# cm5.net
KiCad netlist of a schematic drawn in Altium Designer
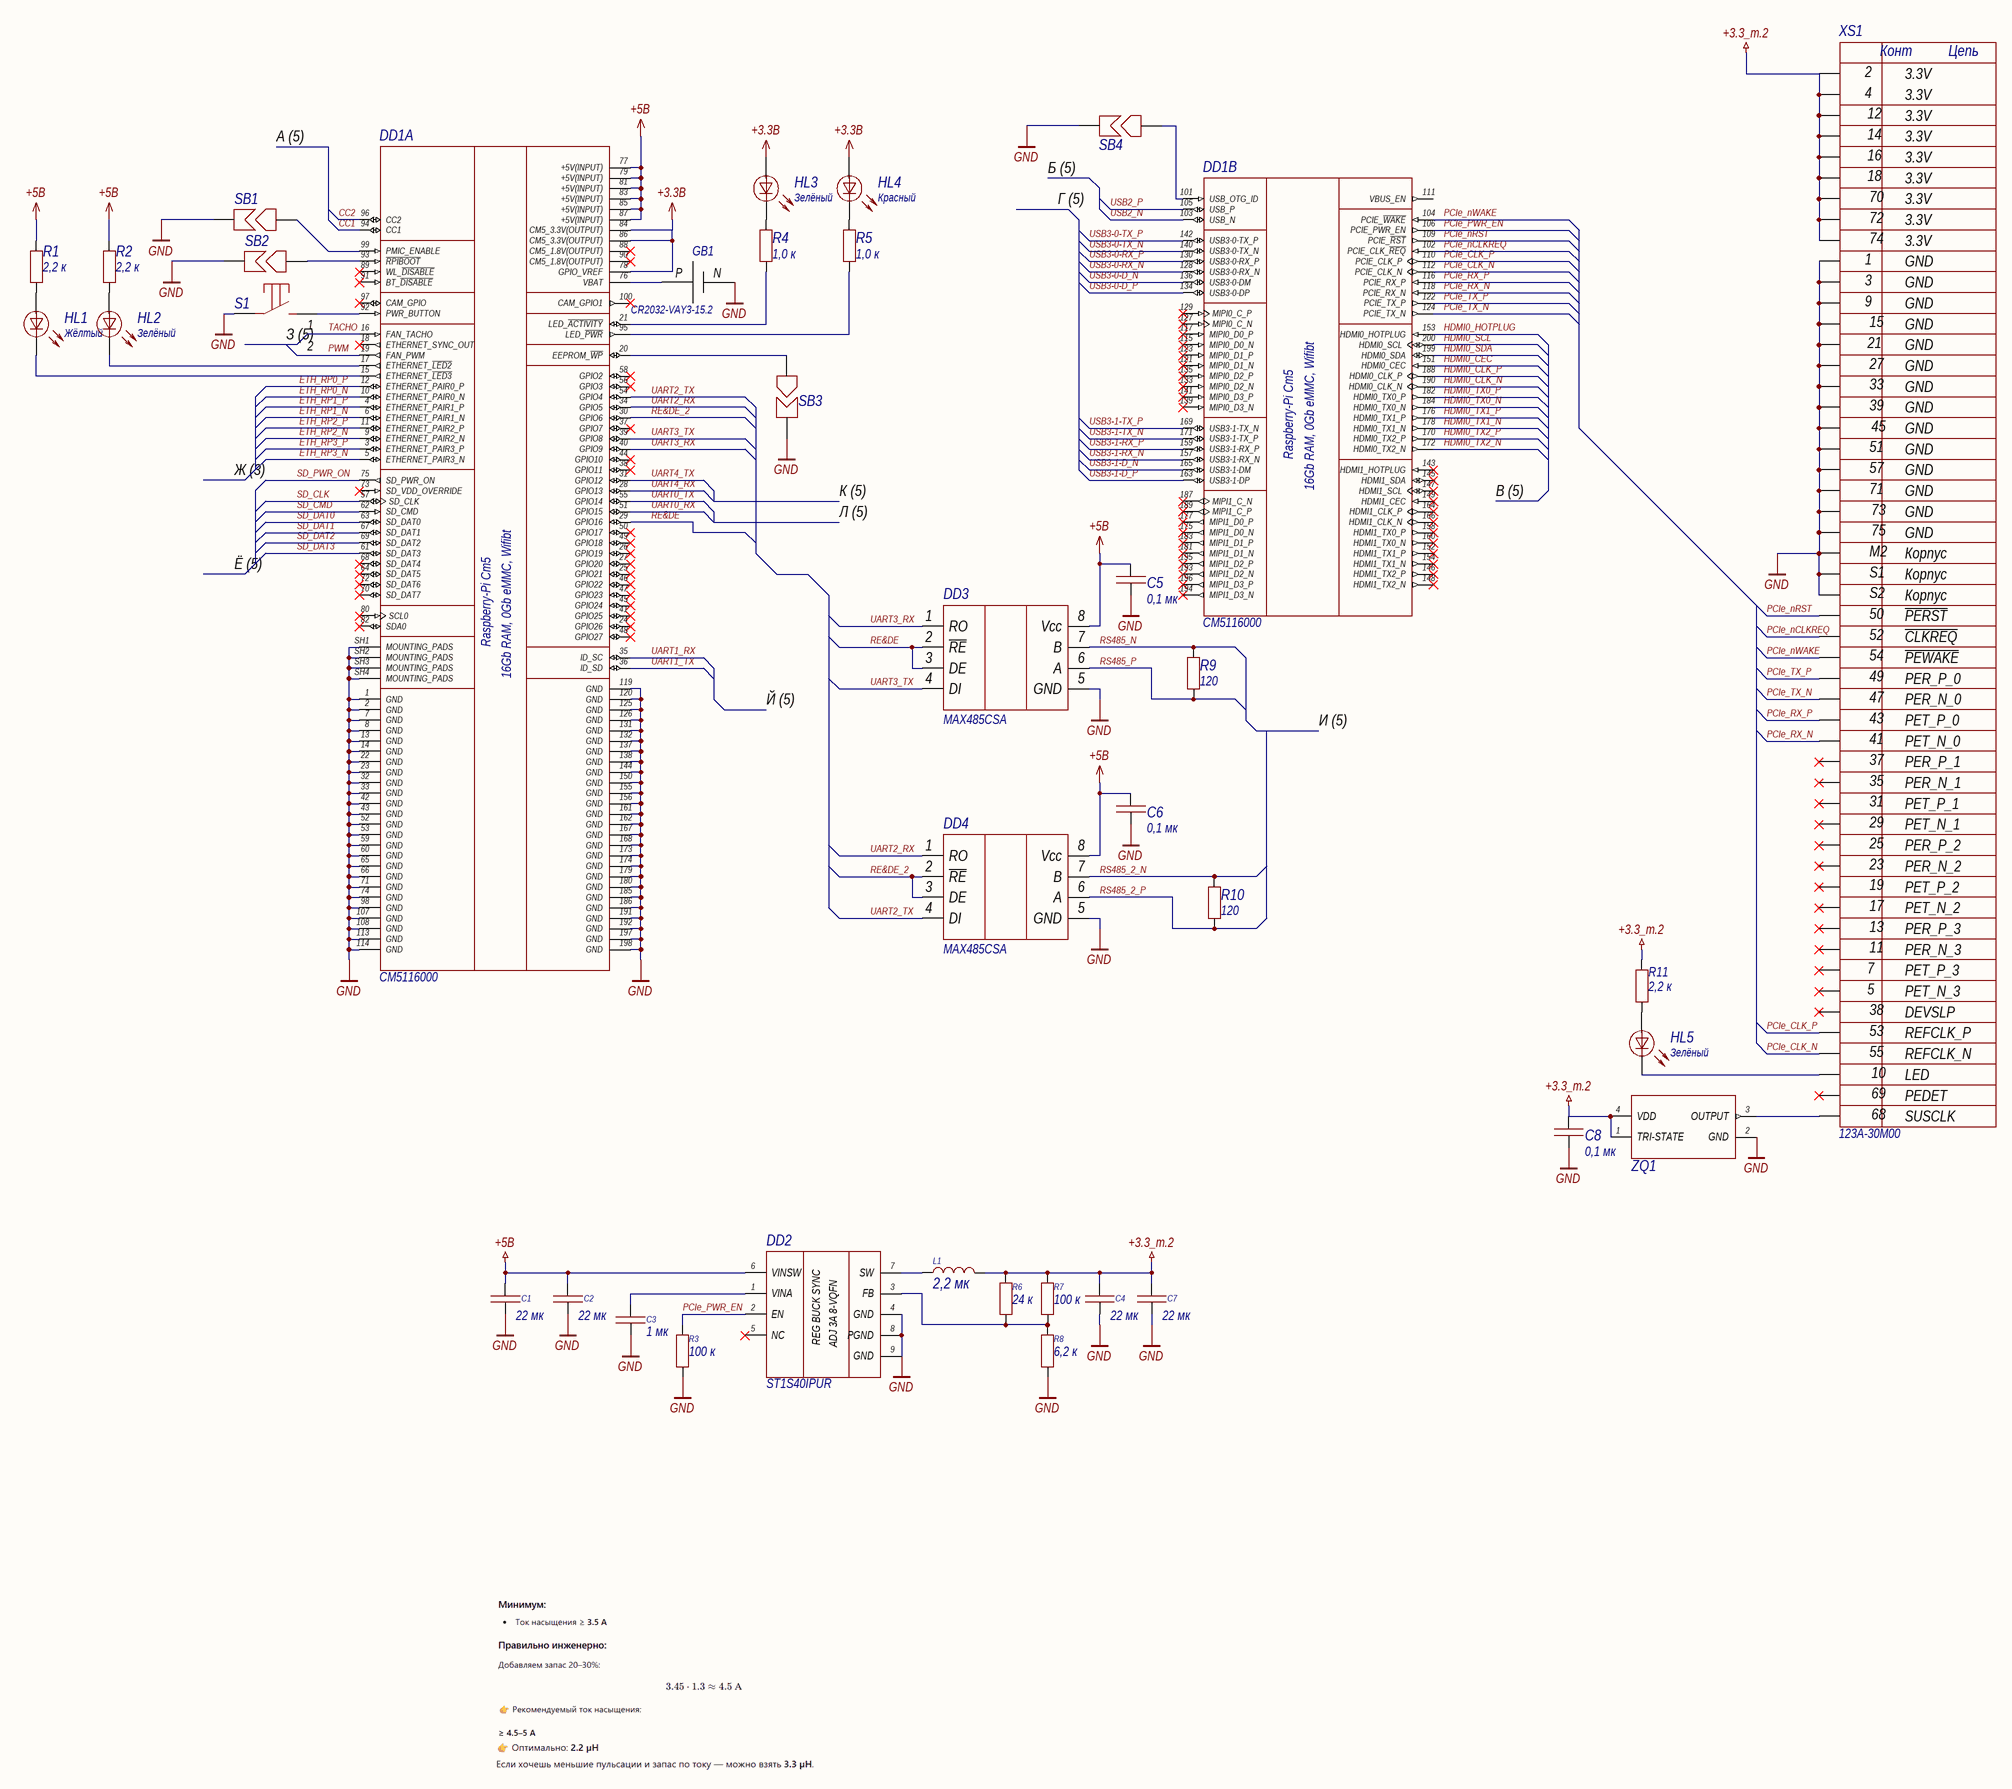
[diagram p0: cm5.SchDoc]

(export (version "E")
  (design (tool "Eeschema 10.0.6"))
  (components
    (comp (ref "C1")
      (value "22 мк")
      (footprint "1210C")
      (description "Конденсатор 1210C ёмкостью 22 мк 10%, 25 В, X7R")
      (fields (field (name "PART NUMBER") "Capacitor_22u_10_25V_X7R_1210C") (field (name "TOLERANCE") "10%"))
      (libsource (lib "Hydrolib") (part "Capacitor"))
    )
    (comp (ref "C2")
      (value "22 мк")
      (footprint "1210C")
      (description "Конденсатор 1210C ёмкостью 22 мк 10%, 25 В, X7R")
      (fields (field (name "PART NUMBER") "Capacitor_22u_10_25V_X7R_1210C") (field (name "TOLERANCE") "10%"))
      (libsource (lib "Hydrolib") (part "Capacitor"))
    )
    (comp (ref "C3")
      (value "1 мк")
      (footprint "0603C")
      (description "Конденсатор 0603C ёмкостью 1 мк 10%, 50 В, X7R")
      (fields (field (name "PART NUMBER") "Capacitor_1u_10_50V_X7R_0603C") (field (name "TOLERANCE") "10%"))
      (libsource (lib "Hydrolib") (part "Capacitor"))
    )
    (comp (ref "C4")
      (value "22 мк")
      (footprint "1210C")
      (description "Конденсатор 1210C ёмкостью 22 мк 10%, 25 В, X7R")
      (fields (field (name "PART NUMBER") "Capacitor_22u_10_25V_X7R_1210C") (field (name "TOLERANCE") "10%"))
      (libsource (lib "Hydrolib") (part "Capacitor"))
    )
    (comp (ref "C5")
      (value "0,1 мк")
      (footprint "0603C")
      (description "Конденсатор 0603C ёмкостью 0,1 мк 10%, 50 В, X7R")
      (fields (field (name "PART NUMBER") "Capacitor_0,1u_10_50V_X7R_0603C") (field (name "TOLERANCE") "10%"))
      (libsource (lib "Hydrolib") (part "Capacitor"))
    )
    (comp (ref "C6")
      (value "0,1 мк")
      (footprint "0603C")
      (description "Конденсатор 0603C ёмкостью 0,1 мк 10%, 50 В, X7R")
      (fields (field (name "PART NUMBER") "Capacitor_0,1u_10_50V_X7R_0603C") (field (name "TOLERANCE") "10%"))
      (libsource (lib "Hydrolib") (part "Capacitor"))
    )
    (comp (ref "C7")
      (value "22 мк")
      (footprint "1210C")
      (description "Конденсатор 1210C ёмкостью 22 мк 10%, 25 В, X7R")
      (fields (field (name "PART NUMBER") "Capacitor_22u_10_25V_X7R_1210C") (field (name "TOLERANCE") "10%"))
      (libsource (lib "Hydrolib") (part "Capacitor"))
    )
    (comp (ref "C8")
      (value "0,1 мк")
      (footprint "0603C")
      (description "Конденсатор 0603C ёмкостью 0,1 мк 10%, 50 В, X7R")
      (fields (field (name "PART NUMBER") "Capacitor_0,1u_10_50V_X7R_0603C") (field (name "TOLERANCE") "10%"))
      (libsource (lib "Hydrolib") (part "Capacitor"))
    )
    (comp (ref "DD1")
      (value "CM5116000")
      (footprint "CM5116000")
      (description "Raspberry-Pi Cm5 16Gb RAM, 0Gb eMMC, Wifibt")
      (fields
        (field (name "MF") "Raspberry Pi")
        (field (name "MP") "CM5108064B")
        (field (name "АВТОР") "rreali")
      )
      (libsource (lib "Hydrolib") (part "CM5116000"))
    )
    (comp (ref "DD2")
      (value "ST1S40IPUR")
      (footprint "VFQFPN8-4X4")
      (description "Преобразователь постоянного тока понижающий синхронный подстраиваемый 3А")
      (fields (field (name "MF") "STMicroelectronics") (field (name "АВТОР") "rreali"))
      (libsource (lib "Hydrolib") (part "ST1S40IPUR"))
    )
    (comp (ref "DD3")
      (value "MAX485CSA")
      (footprint "SOIC-8")
      (description "RS-485 приёмопередатчик")
      (libsource (lib "Hydrolib") (part "MAX485CSA"))
    )
    (comp (ref "DD4")
      (value "MAX485CSA")
      (footprint "SOIC-8")
      (description "RS-485 приёмопередатчик")
      (libsource (lib "Hydrolib") (part "MAX485CSA"))
    )
    (comp (ref "GB1")
      (value "CR2032-VAY3-15.2")
      (footprint "CR2032-VAY3-15.2")
      (description "Li, MnO2 батарея типоразмера R20, 3В, 0.22Ач, приваренные выводы, -20...60 °C")
      (fields (field (name "АВТОР") "rreali"))
      (libsource (lib "Hydrolib") (part "Battery"))
    )
    (comp (ref "HL1")
      (value "Жёлтый")
      (footprint "0603D_yellow")
      (description "Светодиод 0603 Жёлтый")
      (fields (field (name "PART NUMBER") "LED 0603 YELLOW") (field (name "АВТОР") "rreali"))
      (libsource (lib "Hydrolib") (part "LED"))
    )
    (comp (ref "HL2")
      (value "Зелёный")
      (footprint "0603D_green")
      (description "Светодиод 0603 Зелёный")
      (fields (field (name "PART NUMBER") "LED 0603 GREEN") (field (name "АВТОР") "rreali"))
      (libsource (lib "Hydrolib") (part "LED"))
    )
    (comp (ref "HL3")
      (value "Зелёный")
      (footprint "0603D_green")
      (description "Светодиод 0603 Зелёный")
      (fields (field (name "PART NUMBER") "LED 0603 GREEN") (field (name "АВТОР") "rreali"))
      (libsource (lib "Hydrolib") (part "LED"))
    )
    (comp (ref "HL4")
      (value "Красный")
      (footprint "0603D_red")
      (description "Светодиод 0603 Красный")
      (fields (field (name "PART NUMBER") "LED 0603 RED") (field (name "АВТОР") "rreali"))
      (libsource (lib "Hydrolib") (part "LED"))
    )
    (comp (ref "HL5")
      (value "Зелёный")
      (footprint "0603D_green")
      (description "Светодиод 0603 Зелёный")
      (fields (field (name "PART NUMBER") "LED 0603 GREEN") (field (name "АВТОР") "rreali"))
      (libsource (lib "Hydrolib") (part "LED"))
    )
    (comp (ref "L1")
      (value "2,2 мк")
      (footprint "IHLP-2020")
      (description "Катушка индуктивности SMD экранированная 2,2мкГн ±20% 4,2A 50,1мОм 2020 лента на катушке")
      (fields (field (name "PART NUMBER") "IHLP2020BZER2R2M01") (field (name "АВТОР") "rreali"))
      (libsource (lib "Hydrolib") (part "Inductance"))
    )
    (comp (ref "R1")
      (value "2,2 к")
      (footprint "0603R")
      (description "Резистор номиналом 2,2 кОм 1%")
      (fields (field (name "PART NUMBER") "Resistor_2.2k_1_0603") (field (name "TOLERANCE") "1%"))
      (libsource (lib "Hydrolib") (part "Resistor"))
    )
    (comp (ref "R2")
      (value "2,2 к")
      (footprint "0603R")
      (description "Резистор номиналом 2,2 кОм 1%")
      (fields (field (name "PART NUMBER") "Resistor_2.2k_1_0603") (field (name "TOLERANCE") "1%"))
      (libsource (lib "Hydrolib") (part "Resistor"))
    )
    (comp (ref "R3")
      (value "100 к")
      (footprint "0603R")
      (description "Резистор номиналом 100 кОм 1%")
      (fields (field (name "PART NUMBER") "Resistor_100k_1_0603") (field (name "TOLERANCE") "1%"))
      (libsource (lib "Hydrolib") (part "Resistor"))
    )
    (comp (ref "R4")
      (value "1,0 к")
      (footprint "0603R")
      (description "Резистор номиналом 1,0 кОм 1%")
      (fields (field (name "PART NUMBER") "Resistor_1.0k_1_0603") (field (name "TOLERANCE") "1%"))
      (libsource (lib "") (part "Resistor_1"))
    )
    (comp (ref "R5")
      (value "1,0 к")
      (footprint "0603R")
      (description "Резистор номиналом 1,0 кОм 1%")
      (fields (field (name "PART NUMBER") "Resistor_1.0k_1_0603") (field (name "TOLERANCE") "1%"))
      (libsource (lib "") (part "Resistor_1"))
    )
    (comp (ref "R6")
      (value "24 к")
      (footprint "0603R")
      (description "Резистор номиналом 24 кОм 1%")
      (fields (field (name "PART NUMBER") "Resistor_24k_1_0603") (field (name "TOLERANCE") "1%"))
      (libsource (lib "Hydrolib") (part "Resistor"))
    )
    (comp (ref "R7")
      (value "100 к")
      (footprint "0603R")
      (description "Резистор номиналом 100 кОм 1%")
      (fields (field (name "PART NUMBER") "Resistor_100k_1_0603") (field (name "TOLERANCE") "1%"))
      (libsource (lib "Hydrolib") (part "Resistor"))
    )
    (comp (ref "R8")
      (value "6,2 к")
      (footprint "0603R")
      (description "Резистор номиналом 6,2 кОм 1%")
      (fields (field (name "PART NUMBER") "Resistor_6.2k_1_0603") (field (name "TOLERANCE") "1%"))
      (libsource (lib "Hydrolib") (part "Resistor"))
    )
    (comp (ref "R9")
      (value "120")
      (footprint "1206R")
      (description "Резистор номиналом 120 Ом 1%")
      (fields (field (name "PART NUMBER") "Resistor_120_1_0603") (field (name "TOLERANCE") "1%"))
      (libsource (lib "Hydrolib") (part "Resistor"))
    )
    (comp (ref "R10")
      (value "120")
      (footprint "1206R")
      (description "Резистор номиналом 120 Ом 1%")
      (fields (field (name "PART NUMBER") "Resistor_120_1_0603") (field (name "TOLERANCE") "1%"))
      (libsource (lib "Hydrolib") (part "Resistor"))
    )
    (comp (ref "R11")
      (value "2,2 к")
      (footprint "0603R")
      (description "Резистор номиналом 2,2 кОм 1%")
      (fields (field (name "PART NUMBER") "Resistor_2.2k_1_0603") (field (name "TOLERANCE") "1%"))
      (libsource (lib "Hydrolib") (part "Resistor"))
    )
    (comp (ref "S1")
      (value "TSS-TD-19XA-XTR")
      (footprint "TSS-TD-19XA-XTR")
      (description "Тактовая кнопка")
      (fields (field (name "АВТОР") "glebmih"))
      (libsource (lib "Hydrolib") (part "Tact_button"))
    )
    (comp (ref "SB1")
      (value "SB")
      (footprint "0603SB")
      (description "Solder bridge, мост припоя, запаиваемая перемычка, net tie, jumper")
      (fields (field (name "АВТОР") "rreali"))
      (libsource (lib "Hydrolib") (part "SB"))
    )
    (comp (ref "SB2")
      (value "SB")
      (footprint "0603SB")
      (description "Solder bridge, мост припоя, запаиваемая перемычка, net tie, jumper")
      (fields (field (name "АВТОР") "rreali"))
      (libsource (lib "Hydrolib") (part "SB"))
    )
    (comp (ref "SB3")
      (value "SB")
      (footprint "0603SB")
      (description "Solder bridge, мост припоя, запаиваемая перемычка, net tie, jumper")
      (fields (field (name "АВТОР") "rreali"))
      (libsource (lib "Hydrolib") (part "SB"))
    )
    (comp (ref "SB4")
      (value "SB")
      (footprint "0603SB")
      (description "Solder bridge, мост припоя, запаиваемая перемычка, net tie, jumper")
      (fields (field (name "АВТОР") "rreali"))
      (libsource (lib "Hydrolib") (part "SB"))
    )
    (comp (ref "XS1")
      (value "123A-30M00")
      (footprint "123A-30M00")
      (description "Разъем: M.2 (NGFF); горизонтальный; SMT; gold flash; PIN: 67; 0,5А")
      (fields (field (name "АВТОР") "rreali"))
      (libsource (lib "Hydrolib") (part "M2"))
    )
    (comp (ref "ZQ1")
      (value "ASEK-32.768KHZ-LRT")
      (footprint "XTAL_ASEK-32.768KHZ-LRT")
      (description "Генератор кварцевый керамика 32.768кГц ±25ppm/°С -40°C....+85В°C SMT")
      (fields (field (name "АВТОР") "rreali"))
      (libsource (lib "Hydrolib") (part "ASEK-32.768KHZ-LRT"))
    )
  )
  (nets
    (net (code "1") (name "+3.3_m.2") (class "Default")
      (node (ref "C4") (pin "2") (pinfunction "2_2") (pintype "passive"))
      (node (ref "C7") (pin "2") (pinfunction "2_2") (pintype "passive"))
      (node (ref "C8") (pin "2") (pinfunction "2_2") (pintype "passive"))
      (node (ref "L1") (pin "2") (pinfunction "2_2") (pintype "passive"))
      (node (ref "R11") (pin "2") (pinfunction "2_2") (pintype "passive"))
      (node (ref "R6") (pin "2") (pinfunction "2_2") (pintype "passive"))
      (node (ref "R7") (pin "2") (pinfunction "2_2") (pintype "passive"))
      (node (ref "XS1") (pin "12") (pinfunction "3.3V_12") (pintype "passive"))
      (node (ref "XS1") (pin "14") (pinfunction "3.3V_14") (pintype "passive"))
      (node (ref "XS1") (pin "16") (pinfunction "3.3V_16") (pintype "passive"))
      (node (ref "XS1") (pin "18") (pinfunction "3.3V_18") (pintype "passive"))
      (node (ref "XS1") (pin "2") (pinfunction "3.3V_2") (pintype "passive"))
      (node (ref "XS1") (pin "4") (pinfunction "3.3V_4") (pintype "passive"))
      (node (ref "XS1") (pin "70") (pinfunction "3.3V_70") (pintype "passive"))
      (node (ref "XS1") (pin "72") (pinfunction "3.3V_72") (pintype "passive"))
      (node (ref "XS1") (pin "74") (pinfunction "3.3V_74") (pintype "passive"))
      (node (ref "ZQ1") (pin "1") (pinfunction "TRI-STATE_1") (pintype "passive"))
      (node (ref "ZQ1") (pin "4") (pinfunction "VDD_4") (pintype "power_in"))
    )
    (net (code "2") (name "+3.3В") (class "Default")
      (node (ref "DD1") (pin "78") (pinfunction "GPIO_VREF_78") (pintype "power_in"))
      (node (ref "DD1") (pin "84") (pinfunction "CM5_3.3V(OUTPUT)_84") (pintype "power_in"))
      (node (ref "DD1") (pin "86") (pinfunction "CM5_3.3V(OUTPUT)_86") (pintype "power_in"))
      (node (ref "HL3") (pin "1") (pinfunction "1_1") (pintype "passive"))
      (node (ref "HL4") (pin "1") (pinfunction "1_1") (pintype "passive"))
    )
    (net (code "3") (name "+5В") (class "Default")
      (node (ref "C1") (pin "2") (pinfunction "2_2") (pintype "passive"))
      (node (ref "C2") (pin "2") (pinfunction "2_2") (pintype "passive"))
      (node (ref "C5") (pin "2") (pinfunction "2_2") (pintype "passive"))
      (node (ref "C6") (pin "2") (pinfunction "2_2") (pintype "passive"))
      (node (ref "DD1") (pin "77") (pinfunction "+5V(INPUT)_77") (pintype "power_in"))
      (node (ref "DD1") (pin "79") (pinfunction "+5V(INPUT)_79") (pintype "power_in"))
      (node (ref "DD1") (pin "81") (pinfunction "+5V(INPUT)_81") (pintype "power_in"))
      (node (ref "DD1") (pin "83") (pinfunction "+5V(INPUT)_83") (pintype "power_in"))
      (node (ref "DD1") (pin "85") (pinfunction "+5V(INPUT)_85") (pintype "power_in"))
      (node (ref "DD1") (pin "87") (pinfunction "+5V(INPUT)_87") (pintype "power_in"))
      (node (ref "DD2") (pin "6") (pinfunction "VINSW_6") (pintype "passive"))
      (node (ref "DD3") (pin "8") (pinfunction "Vcc_8") (pintype "passive"))
      (node (ref "DD4") (pin "8") (pinfunction "Vcc_8") (pintype "passive"))
      (node (ref "R1") (pin "2") (pinfunction "2_2") (pintype "passive"))
      (node (ref "R2") (pin "2") (pinfunction "2_2") (pintype "passive"))
    )
    (net (code "4") (name "/CC1") (class "Default")
      (node (ref "DD1") (pin "94") (pinfunction "CC1_94") (pintype "bidirectional"))
    )
    (net (code "5") (name "/CC2") (class "Default")
      (node (ref "DD1") (pin "96") (pinfunction "CC2_96") (pintype "bidirectional"))
    )
    (net (code "6") (name "/ETH_RP0_N") (class "Default")
      (node (ref "DD1") (pin "10") (pinfunction "ETHERNET_PAIR0_N_10") (pintype "bidirectional"))
    )
    (net (code "7") (name "/ETH_RP0_P") (class "Default")
      (node (ref "DD1") (pin "12") (pinfunction "ETHERNET_PAIR0_P_12") (pintype "bidirectional"))
    )
    (net (code "8") (name "/ETH_RP1_N") (class "Default")
      (node (ref "DD1") (pin "6") (pinfunction "ETHERNET_PAIR1_N_6") (pintype "bidirectional"))
    )
    (net (code "9") (name "/ETH_RP1_P") (class "Default")
      (node (ref "DD1") (pin "4") (pinfunction "ETHERNET_PAIR1_P_4") (pintype "bidirectional"))
    )
    (net (code "10") (name "/ETH_RP2_N") (class "Default")
      (node (ref "DD1") (pin "9") (pinfunction "ETHERNET_PAIR2_N_9") (pintype "bidirectional"))
    )
    (net (code "11") (name "/ETH_RP2_P") (class "Default")
      (node (ref "DD1") (pin "11") (pinfunction "ETHERNET_PAIR2_P_11") (pintype "bidirectional"))
    )
    (net (code "12") (name "/ETH_RP3_N") (class "Default")
      (node (ref "DD1") (pin "5") (pinfunction "ETHERNET_PAIR3_N_5") (pintype "bidirectional"))
    )
    (net (code "13") (name "/ETH_RP3_P") (class "Default")
      (node (ref "DD1") (pin "3") (pinfunction "ETHERNET_PAIR3_P_3") (pintype "bidirectional"))
    )
    (net (code "14") (name "/HDMI0_CEC") (class "Default")
      (node (ref "DD1") (pin "151") (pinfunction "HDMI0_CEC_151") (pintype "input"))
    )
    (net (code "15") (name "/HDMI0_CLK_N") (class "Default")
      (node (ref "DD1") (pin "190") (pinfunction "HDMI0_CLK_N_190") (pintype "output"))
    )
    (net (code "16") (name "/HDMI0_CLK_P") (class "Default")
      (node (ref "DD1") (pin "188") (pinfunction "HDMI0_CLK_P_188") (pintype "output"))
    )
    (net (code "17") (name "/HDMI0_HOTPLUG") (class "Default")
      (node (ref "DD1") (pin "153") (pinfunction "HDMI0_HOTPLUG_153") (pintype "input"))
    )
    (net (code "18") (name "/HDMI0_SCL") (class "Default")
      (node (ref "DD1") (pin "200") (pinfunction "HDMI0_SCL_200") (pintype "bidirectional"))
    )
    (net (code "19") (name "/HDMI0_SDA") (class "Default")
      (node (ref "DD1") (pin "199") (pinfunction "HDMI0_SDA_199") (pintype "bidirectional"))
    )
    (net (code "20") (name "/HDMI0_TX0_N") (class "Default")
      (node (ref "DD1") (pin "184") (pinfunction "HDMI0_TX0_N_184") (pintype "output"))
    )
    (net (code "21") (name "/HDMI0_TX0_P") (class "Default")
      (node (ref "DD1") (pin "182") (pinfunction "HDMI0_TX0_P_182") (pintype "output"))
    )
    (net (code "22") (name "/HDMI0_TX1_N") (class "Default")
      (node (ref "DD1") (pin "178") (pinfunction "HDMI0_TX1_N_178") (pintype "output"))
    )
    (net (code "23") (name "/HDMI0_TX1_P") (class "Default")
      (node (ref "DD1") (pin "176") (pinfunction "HDMI0_TX1_P_176") (pintype "output"))
    )
    (net (code "24") (name "/HDMI0_TX2_N") (class "Default")
      (node (ref "DD1") (pin "172") (pinfunction "HDMI0_TX2_N_172") (pintype "output"))
    )
    (net (code "25") (name "/HDMI0_TX2_P") (class "Default")
      (node (ref "DD1") (pin "170") (pinfunction "HDMI0_TX2_P_170") (pintype "output"))
    )
    (net (code "26") (name "/PCIe_CLK_N") (class "Default")
      (node (ref "DD1") (pin "112") (pinfunction "PCIE_CLK_N_112") (pintype "output"))
      (node (ref "XS1") (pin "55") (pinfunction "REFCLK_N_55") (pintype "passive"))
    )
    (net (code "27") (name "/PCIe_CLK_P") (class "Default")
      (node (ref "DD1") (pin "110") (pinfunction "PCIE_CLK_P_110") (pintype "output"))
      (node (ref "XS1") (pin "53") (pinfunction "REFCLK_P_53") (pintype "passive"))
    )
    (net (code "28") (name "/PCIe_PWR_EN") (class "Default")
      (node (ref "DD1") (pin "106") (pinfunction "PCIE_PWR_EN_106") (pintype "output"))
      (node (ref "DD2") (pin "2") (pinfunction "EN_2") (pintype "passive"))
      (node (ref "R3") (pin "2") (pinfunction "2_2") (pintype "passive"))
    )
    (net (code "29") (name "/PCIe_RX_N") (class "Default")
      (node (ref "DD1") (pin "118") (pinfunction "PCIE_RX_N_118") (pintype "input"))
      (node (ref "XS1") (pin "41") (pinfunction "PET_N_0_41") (pintype "passive"))
    )
    (net (code "30") (name "/PCIe_RX_P") (class "Default")
      (node (ref "DD1") (pin "116") (pinfunction "PCIE_RX_P_116") (pintype "input"))
      (node (ref "XS1") (pin "43") (pinfunction "PET_P_0_43") (pintype "passive"))
    )
    (net (code "31") (name "/PCIe_TX_N") (class "Default")
      (node (ref "DD1") (pin "124") (pinfunction "PCIE_TX_N_124") (pintype "output"))
      (node (ref "XS1") (pin "47") (pinfunction "PER_N_0_47") (pintype "passive"))
    )
    (net (code "32") (name "/PCIe_TX_P") (class "Default")
      (node (ref "DD1") (pin "122") (pinfunction "PCIE_TX_P_122") (pintype "output"))
      (node (ref "XS1") (pin "49") (pinfunction "PER_P_0_49") (pintype "passive"))
    )
    (net (code "33") (name "/PCIe_nCLKREQ") (class "Default")
      (node (ref "DD1") (pin "102") (pinfunction "PCIE_CLK_~{REQ}_102") (pintype "input"))
      (node (ref "XS1") (pin "52") (pinfunction "~{CLKREQ}_52") (pintype "passive"))
    )
    (net (code "34") (name "/PCIe_nRST") (class "Default")
      (node (ref "DD1") (pin "109") (pinfunction "PCIE_~{RST}_109") (pintype "output"))
      (node (ref "XS1") (pin "50") (pinfunction "~{PERST}_50") (pintype "passive"))
    )
    (net (code "35") (name "/PCIe_nWAKE") (class "Default")
      (node (ref "DD1") (pin "104") (pinfunction "PCIE_~{WAKE}_104") (pintype "input"))
      (node (ref "XS1") (pin "54") (pinfunction "~{PEWAKE}_54") (pintype "passive"))
    )
    (net (code "36") (name "/PWM") (class "Default")
      (node (ref "DD1") (pin "19") (pinfunction "FAN_PWM_19") (pintype "output"))
    )
    (net (code "37") (name "/RE&DE") (class "Default")
      (node (ref "DD1") (pin "29") (pinfunction "GPIO16_29") (pintype "bidirectional"))
      (node (ref "DD3") (pin "2") (pinfunction "RE_2") (pintype "passive"))
      (node (ref "DD3") (pin "3") (pinfunction "DE_3") (pintype "passive"))
    )
    (net (code "38") (name "/RE&DE_2") (class "Default")
      (node (ref "DD1") (pin "30") (pinfunction "GPIO6_30") (pintype "bidirectional"))
      (node (ref "DD4") (pin "2") (pinfunction "RE_2") (pintype "passive"))
      (node (ref "DD4") (pin "3") (pinfunction "DE_3") (pintype "passive"))
    )
    (net (code "39") (name "/RS485_2_N") (class "Default")
      (node (ref "DD4") (pin "7") (pinfunction "B_7") (pintype "passive"))
      (node (ref "R10") (pin "2") (pinfunction "2_2") (pintype "passive"))
    )
    (net (code "40") (name "/RS485_2_P") (class "Default")
      (node (ref "DD4") (pin "6") (pinfunction "A_6") (pintype "passive"))
      (node (ref "R10") (pin "1") (pinfunction "1_1") (pintype "passive"))
    )
    (net (code "41") (name "/RS485_N") (class "Default")
      (node (ref "DD3") (pin "7") (pinfunction "B_7") (pintype "passive"))
      (node (ref "R9") (pin "2") (pinfunction "2_2") (pintype "passive"))
    )
    (net (code "42") (name "/RS485_P") (class "Default")
      (node (ref "DD3") (pin "6") (pinfunction "A_6") (pintype "passive"))
      (node (ref "R9") (pin "1") (pinfunction "1_1") (pintype "passive"))
    )
    (net (code "43") (name "/SD_CLK") (class "Default")
      (node (ref "DD1") (pin "57") (pinfunction "SD_CLK_57") (pintype "bidirectional"))
    )
    (net (code "44") (name "/SD_CMD") (class "Default")
      (node (ref "DD1") (pin "62") (pinfunction "SD_CMD_62") (pintype "input"))
    )
    (net (code "45") (name "/SD_DAT0") (class "Default")
      (node (ref "DD1") (pin "63") (pinfunction "SD_DAT0_63") (pintype "bidirectional"))
    )
    (net (code "46") (name "/SD_DAT1") (class "Default")
      (node (ref "DD1") (pin "67") (pinfunction "SD_DAT1_67") (pintype "bidirectional"))
    )
    (net (code "47") (name "/SD_DAT2") (class "Default")
      (node (ref "DD1") (pin "69") (pinfunction "SD_DAT2_69") (pintype "bidirectional"))
    )
    (net (code "48") (name "/SD_DAT3") (class "Default")
      (node (ref "DD1") (pin "61") (pinfunction "SD_DAT3_61") (pintype "bidirectional"))
    )
    (net (code "49") (name "/SD_PWR_ON") (class "Default")
      (node (ref "DD1") (pin "75") (pinfunction "SD_PWR_ON_75") (pintype "output"))
    )
    (net (code "50") (name "/TACHO") (class "Default")
      (node (ref "DD1") (pin "16") (pinfunction "FAN_TACHO_16") (pintype "input"))
    )
    (net (code "51") (name "/UART0_RX") (class "Default")
      (node (ref "DD1") (pin "51") (pinfunction "GPIO15_51") (pintype "bidirectional"))
    )
    (net (code "52") (name "/UART0_TX") (class "Default")
      (node (ref "DD1") (pin "55") (pinfunction "GPIO14_55") (pintype "bidirectional"))
    )
    (net (code "53") (name "/UART1_RX") (class "Default")
      (node (ref "DD1") (pin "35") (pinfunction "ID_SC_35") (pintype "bidirectional"))
    )
    (net (code "54") (name "/UART1_TX") (class "Default")
      (node (ref "DD1") (pin "36") (pinfunction "ID_SD_36") (pintype "bidirectional"))
    )
    (net (code "55") (name "/UART2_RX") (class "Default")
      (node (ref "DD1") (pin "34") (pinfunction "GPIO5_34") (pintype "bidirectional"))
      (node (ref "DD4") (pin "1") (pinfunction "RO_1") (pintype "passive"))
    )
    (net (code "56") (name "/UART2_TX") (class "Default")
      (node (ref "DD1") (pin "54") (pinfunction "GPIO4_54") (pintype "bidirectional"))
      (node (ref "DD4") (pin "4") (pinfunction "DI_4") (pintype "passive"))
    )
    (net (code "57") (name "/UART3_RX") (class "Default")
      (node (ref "DD1") (pin "40") (pinfunction "GPIO9_40") (pintype "bidirectional"))
      (node (ref "DD3") (pin "1") (pinfunction "RO_1") (pintype "passive"))
    )
    (net (code "58") (name "/UART3_TX") (class "Default")
      (node (ref "DD1") (pin "39") (pinfunction "GPIO8_39") (pintype "bidirectional"))
      (node (ref "DD3") (pin "4") (pinfunction "DI_4") (pintype "passive"))
    )
    (net (code "59") (name "/UART4_RX") (class "Default")
      (node (ref "DD1") (pin "28") (pinfunction "GPIO13_28") (pintype "bidirectional"))
    )
    (net (code "60") (name "/UART4_TX") (class "Default")
      (node (ref "DD1") (pin "31") (pinfunction "GPIO12_31") (pintype "bidirectional"))
    )
    (net (code "61") (name "/USB2_N") (class "Default")
      (node (ref "DD1") (pin "103") (pinfunction "USB_N_103") (pintype "bidirectional"))
    )
    (net (code "62") (name "/USB2_P") (class "Default")
      (node (ref "DD1") (pin "105") (pinfunction "USB_P_105") (pintype "bidirectional"))
    )
    (net (code "63") (name "/USB3-0-D_N") (class "Default")
      (node (ref "DD1") (pin "136") (pinfunction "USB3-0-DM_136") (pintype "bidirectional"))
    )
    (net (code "64") (name "/USB3-0-D_P") (class "Default")
      (node (ref "DD1") (pin "134") (pinfunction "USB3-0-DP_134") (pintype "bidirectional"))
    )
    (net (code "65") (name "/USB3-0-RX_N") (class "Default")
      (node (ref "DD1") (pin "128") (pinfunction "USB3-0-RX_N_128") (pintype "bidirectional"))
    )
    (net (code "66") (name "/USB3-0-RX_P") (class "Default")
      (node (ref "DD1") (pin "130") (pinfunction "USB3-0-RX_P_130") (pintype "bidirectional"))
    )
    (net (code "67") (name "/USB3-0-TX_N") (class "Default")
      (node (ref "DD1") (pin "140") (pinfunction "USB3-0-TX_N_140") (pintype "bidirectional"))
    )
    (net (code "68") (name "/USB3-0-TX_P") (class "Default")
      (node (ref "DD1") (pin "142") (pinfunction "USB3-0-TX_P_142") (pintype "bidirectional"))
    )
    (net (code "69") (name "/USB3-1-D_N") (class "Default")
      (node (ref "DD1") (pin "165") (pinfunction "USB3-1-DM_165") (pintype "bidirectional"))
    )
    (net (code "70") (name "/USB3-1-D_P") (class "Default")
      (node (ref "DD1") (pin "163") (pinfunction "USB3-1-DP_163") (pintype "bidirectional"))
    )
    (net (code "71") (name "/USB3-1-RX_N") (class "Default")
      (node (ref "DD1") (pin "157") (pinfunction "USB3-1-RX_N_157") (pintype "bidirectional"))
    )
    (net (code "72") (name "/USB3-1-RX_P") (class "Default")
      (node (ref "DD1") (pin "159") (pinfunction "USB3-1-RX_P_159") (pintype "bidirectional"))
    )
    (net (code "73") (name "/USB3-1-TX_N") (class "Default")
      (node (ref "DD1") (pin "171") (pinfunction "USB3-1-TX_P_171") (pintype "bidirectional"))
    )
    (net (code "74") (name "/USB3-1-TX_P") (class "Default")
      (node (ref "DD1") (pin "169") (pinfunction "USB3-1-TX_N_169") (pintype "bidirectional"))
    )
    (net (code "75") (name "GND") (class "Default")
      (node (ref "C1") (pin "1") (pinfunction "1_1") (pintype "passive"))
      (node (ref "C2") (pin "1") (pinfunction "1_1") (pintype "passive"))
      (node (ref "C3") (pin "1") (pinfunction "1_1") (pintype "passive"))
      (node (ref "C4") (pin "1") (pinfunction "1_1") (pintype "passive"))
      (node (ref "C5") (pin "1") (pinfunction "1_1") (pintype "passive"))
      (node (ref "C6") (pin "1") (pinfunction "1_1") (pintype "passive"))
      (node (ref "C7") (pin "1") (pinfunction "1_1") (pintype "passive"))
      (node (ref "C8") (pin "1") (pinfunction "1_1") (pintype "passive"))
      (node (ref "DD1") (pin "1") (pinfunction "GND_1") (pintype "power_in"))
      (node (ref "DD1") (pin "107") (pinfunction "GND_107") (pintype "power_in"))
      (node (ref "DD1") (pin "108") (pinfunction "GND_108") (pintype "power_in"))
      (node (ref "DD1") (pin "113") (pinfunction "GND_113") (pintype "power_in"))
      (node (ref "DD1") (pin "114") (pinfunction "GND_114") (pintype "power_in"))
      (node (ref "DD1") (pin "119") (pinfunction "GND_119") (pintype "power_in"))
      (node (ref "DD1") (pin "120") (pinfunction "GND_120") (pintype "power_in"))
      (node (ref "DD1") (pin "125") (pinfunction "GND_125") (pintype "power_in"))
      (node (ref "DD1") (pin "126") (pinfunction "GND_126") (pintype "power_in"))
      (node (ref "DD1") (pin "13") (pinfunction "GND_13") (pintype "power_in"))
      (node (ref "DD1") (pin "131") (pinfunction "GND_131") (pintype "power_in"))
      (node (ref "DD1") (pin "132") (pinfunction "GND_132") (pintype "power_in"))
      (node (ref "DD1") (pin "137") (pinfunction "GND_137") (pintype "power_in"))
      (node (ref "DD1") (pin "138") (pinfunction "GND_138") (pintype "power_in"))
      (node (ref "DD1") (pin "14") (pinfunction "GND_14") (pintype "power_in"))
      (node (ref "DD1") (pin "144") (pinfunction "GND_144") (pintype "power_in"))
      (node (ref "DD1") (pin "150") (pinfunction "GND_150") (pintype "power_in"))
      (node (ref "DD1") (pin "155") (pinfunction "GND_155") (pintype "power_in"))
      (node (ref "DD1") (pin "156") (pinfunction "GND_156") (pintype "power_in"))
      (node (ref "DD1") (pin "161") (pinfunction "GND_161") (pintype "power_in"))
      (node (ref "DD1") (pin "162") (pinfunction "GND_162") (pintype "power_in"))
      (node (ref "DD1") (pin "167") (pinfunction "GND_167") (pintype "power_in"))
      (node (ref "DD1") (pin "168") (pinfunction "GND_168") (pintype "power_in"))
      (node (ref "DD1") (pin "173") (pinfunction "GND_173") (pintype "power_in"))
      (node (ref "DD1") (pin "174") (pinfunction "GND_174") (pintype "power_in"))
      (node (ref "DD1") (pin "179") (pinfunction "GND_179") (pintype "power_in"))
      (node (ref "DD1") (pin "180") (pinfunction "GND_180") (pintype "power_in"))
      (node (ref "DD1") (pin "185") (pinfunction "GND_185") (pintype "power_in"))
      (node (ref "DD1") (pin "186") (pinfunction "GND_186") (pintype "power_in"))
      (node (ref "DD1") (pin "191") (pinfunction "GND_191") (pintype "power_in"))
      (node (ref "DD1") (pin "192") (pinfunction "GND_192") (pintype "power_in"))
      (node (ref "DD1") (pin "197") (pinfunction "GND_197") (pintype "power_in"))
      (node (ref "DD1") (pin "198") (pinfunction "GND_198") (pintype "power_in"))
      (node (ref "DD1") (pin "2") (pinfunction "GND_2") (pintype "power_in"))
      (node (ref "DD1") (pin "22") (pinfunction "GND_22") (pintype "power_in"))
      (node (ref "DD1") (pin "23") (pinfunction "GND_23") (pintype "power_in"))
      (node (ref "DD1") (pin "32") (pinfunction "GND_32") (pintype "power_in"))
      (node (ref "DD1") (pin "33") (pinfunction "GND_33") (pintype "power_in"))
      (node (ref "DD1") (pin "42") (pinfunction "GND_42") (pintype "power_in"))
      (node (ref "DD1") (pin "43") (pinfunction "GND_43") (pintype "power_in"))
      (node (ref "DD1") (pin "52") (pinfunction "GND_52") (pintype "power_in"))
      (node (ref "DD1") (pin "53") (pinfunction "GND_53") (pintype "power_in"))
      (node (ref "DD1") (pin "59") (pinfunction "GND_59") (pintype "power_in"))
      (node (ref "DD1") (pin "60") (pinfunction "GND_60") (pintype "power_in"))
      (node (ref "DD1") (pin "65") (pinfunction "GND_65") (pintype "power_in"))
      (node (ref "DD1") (pin "66") (pinfunction "GND_66") (pintype "power_in"))
      (node (ref "DD1") (pin "7") (pinfunction "GND_7") (pintype "power_in"))
      (node (ref "DD1") (pin "71") (pinfunction "GND_71") (pintype "power_in"))
      (node (ref "DD1") (pin "74") (pinfunction "GND_74") (pintype "power_in"))
      (node (ref "DD1") (pin "8") (pinfunction "GND_8") (pintype "power_in"))
      (node (ref "DD1") (pin "98") (pinfunction "GND_98") (pintype "power_in"))
      (node (ref "DD1") (pin "SH1") (pinfunction "MOUNTING_PADS_SH1") (pintype "passive"))
      (node (ref "DD1") (pin "SH2") (pinfunction "MOUNTING_PADS_SH2") (pintype "passive"))
      (node (ref "DD1") (pin "SH3") (pinfunction "MOUNTING_PADS_SH3") (pintype "passive"))
      (node (ref "DD1") (pin "SH4") (pinfunction "MOUNTING_PADS_SH4") (pintype "passive"))
      (node (ref "DD2") (pin "4") (pinfunction "GND_4") (pintype "passive"))
      (node (ref "DD2") (pin "8") (pinfunction "PGND_8") (pintype "passive"))
      (node (ref "DD2") (pin "9") (pinfunction "GND_9") (pintype "passive"))
      (node (ref "DD3") (pin "5") (pinfunction "GND_5") (pintype "passive"))
      (node (ref "DD4") (pin "5") (pinfunction "GND_5") (pintype "passive"))
      (node (ref "GB1") (pin "N") (pinfunction "N_N") (pintype "passive"))
      (node (ref "R3") (pin "1") (pinfunction "1_1") (pintype "passive"))
      (node (ref "R8") (pin "1") (pinfunction "1_1") (pintype "passive"))
      (node (ref "S1") (pin "1") (pinfunction "1_1") (pintype "passive"))
      (node (ref "SB1") (pin "2") (pinfunction "2_2") (pintype "passive"))
      (node (ref "SB2") (pin "2") (pinfunction "2_2") (pintype "passive"))
      (node (ref "SB3") (pin "2") (pinfunction "2_2") (pintype "passive"))
      (node (ref "SB4") (pin "2") (pinfunction "2_2") (pintype "passive"))
      (node (ref "XS1") (pin "1") (pinfunction "GND_1") (pintype "passive"))
      (node (ref "XS1") (pin "15") (pinfunction "GND_15") (pintype "passive"))
      (node (ref "XS1") (pin "21") (pinfunction "GND_21") (pintype "passive"))
      (node (ref "XS1") (pin "27") (pinfunction "GND_27") (pintype "passive"))
      (node (ref "XS1") (pin "3") (pinfunction "GND_3") (pintype "passive"))
      (node (ref "XS1") (pin "33") (pinfunction "GND_33") (pintype "passive"))
      (node (ref "XS1") (pin "39") (pinfunction "GND_39") (pintype "passive"))
      (node (ref "XS1") (pin "45") (pinfunction "GND_45") (pintype "passive"))
      (node (ref "XS1") (pin "51") (pinfunction "GND_51") (pintype "passive"))
      (node (ref "XS1") (pin "57") (pinfunction "GND_57") (pintype "passive"))
      (node (ref "XS1") (pin "71") (pinfunction "GND_71") (pintype "passive"))
      (node (ref "XS1") (pin "73") (pinfunction "GND_73") (pintype "passive"))
      (node (ref "XS1") (pin "75") (pinfunction "GND_75") (pintype "passive"))
      (node (ref "XS1") (pin "9") (pinfunction "GND_9") (pintype "passive"))
      (node (ref "XS1") (pin "M2") (pinfunction "Корпус_M2") (pintype "passive"))
      (node (ref "XS1") (pin "S1") (pinfunction "Корпус_S1") (pintype "passive"))
      (node (ref "XS1") (pin "S2") (pinfunction "Корпус_S2") (pintype "passive"))
      (node (ref "ZQ1") (pin "2") (pinfunction "GND_2") (pintype "passive"))
    )
    (net (code "76") (name "Net-(DD1A-EEPROM_~{WP})") (class "Default")
      (node (ref "DD1") (pin "20") (pinfunction "EEPROM_~{WP}_20") (pintype "bidirectional"))
      (node (ref "SB3") (pin "1") (pinfunction "1_1") (pintype "passive"))
    )
    (net (code "77") (name "Net-(DD1A-ETHERNET_~{LED2})") (class "Default")
      (node (ref "DD1") (pin "17") (pinfunction "ETHERNET_~{LED2}_17") (pintype "output"))
      (node (ref "HL2") (pin "2") (pinfunction "2_2") (pintype "passive"))
    )
    (net (code "78") (name "Net-(DD1A-ETHERNET_~{LED3})") (class "Default")
      (node (ref "DD1") (pin "15") (pinfunction "ETHERNET_~{LED3}_15") (pintype "output"))
      (node (ref "HL1") (pin "2") (pinfunction "2_2") (pintype "passive"))
    )
    (net (code "79") (name "Net-(DD1A-LED_~{ACTIVITY})") (class "Default")
      (node (ref "DD1") (pin "21") (pinfunction "LED_~{ACTIVITY}_21") (pintype "bidirectional"))
      (node (ref "R4") (pin "2") (pinfunction "2_2") (pintype "passive"))
    )
    (net (code "80") (name "Net-(DD1A-LED_~{PWR})") (class "Default")
      (node (ref "DD1") (pin "95") (pinfunction "LED_~{PWR}_95") (pintype "output"))
      (node (ref "R5") (pin "2") (pinfunction "2_2") (pintype "passive"))
    )
    (net (code "81") (name "Net-(DD1A-PMIC_ENABLE)") (class "Default")
      (node (ref "DD1") (pin "99") (pinfunction "PMIC_ENABLE_99") (pintype "input"))
      (node (ref "SB1") (pin "1") (pinfunction "1_1") (pintype "passive"))
    )
    (net (code "82") (name "Net-(DD1A-PWR_BUTTON)") (class "Default")
      (node (ref "DD1") (pin "92") (pinfunction "PWR_BUTTON_92") (pintype "input"))
      (node (ref "S1") (pin "2") (pinfunction "2_2") (pintype "passive"))
    )
    (net (code "83") (name "Net-(DD1A-VBAT)") (class "Default")
      (node (ref "DD1") (pin "76") (pinfunction "VBAT_76") (pintype "power_in"))
      (node (ref "GB1") (pin "P") (pinfunction "P_P") (pintype "passive"))
    )
    (net (code "84") (name "Net-(DD1A-~{RPIBOOT})") (class "Default")
      (node (ref "DD1") (pin "93") (pinfunction "~{RPIBOOT}_93") (pintype "input"))
      (node (ref "SB2") (pin "1") (pinfunction "1_1") (pintype "passive"))
    )
    (net (code "85") (name "Net-(DD1B-USB_OTG_ID)") (class "Default")
      (node (ref "DD1") (pin "101") (pinfunction "USB_OTG_ID_101") (pintype "input"))
      (node (ref "SB4") (pin "1") (pinfunction "1_1") (pintype "passive"))
    )
    (net (code "86") (name "Net-(DD2-FB)") (class "Default")
      (node (ref "DD2") (pin "3") (pinfunction "FB_3") (pintype "passive"))
      (node (ref "R6") (pin "1") (pinfunction "1_1") (pintype "passive"))
      (node (ref "R7") (pin "1") (pinfunction "1_1") (pintype "passive"))
      (node (ref "R8") (pin "2") (pinfunction "2_2") (pintype "passive"))
    )
    (net (code "87") (name "Net-(DD2-SW)") (class "Default")
      (node (ref "DD2") (pin "7") (pinfunction "SW_7") (pintype "passive"))
      (node (ref "L1") (pin "1") (pinfunction "1_1") (pintype "passive"))
    )
    (net (code "88") (name "Net-(DD2-VINA)") (class "Default")
      (node (ref "C3") (pin "2") (pinfunction "2_2") (pintype "passive"))
      (node (ref "DD2") (pin "1") (pinfunction "VINA_1") (pintype "passive"))
    )
    (net (code "89") (name "Net-(HL1-Pad1)") (class "Default")
      (node (ref "HL1") (pin "1") (pinfunction "1_1") (pintype "passive"))
      (node (ref "R1") (pin "1") (pinfunction "1_1") (pintype "passive"))
    )
    (net (code "90") (name "Net-(HL2-Pad1)") (class "Default")
      (node (ref "HL2") (pin "1") (pinfunction "1_1") (pintype "passive"))
      (node (ref "R2") (pin "1") (pinfunction "1_1") (pintype "passive"))
    )
    (net (code "91") (name "Net-(HL3-Pad2)") (class "Default")
      (node (ref "HL3") (pin "2") (pinfunction "2_2") (pintype "passive"))
      (node (ref "R4") (pin "1") (pinfunction "1_1") (pintype "passive"))
    )
    (net (code "92") (name "Net-(HL4-Pad2)") (class "Default")
      (node (ref "HL4") (pin "2") (pinfunction "2_2") (pintype "passive"))
      (node (ref "R5") (pin "1") (pinfunction "1_1") (pintype "passive"))
    )
    (net (code "93") (name "Net-(HL5-Pad1)") (class "Default")
      (node (ref "HL5") (pin "1") (pinfunction "1_1") (pintype "passive"))
      (node (ref "R11") (pin "1") (pinfunction "1_1") (pintype "passive"))
    )
    (net (code "94") (name "Net-(XS1-LED)") (class "Default")
      (node (ref "HL5") (pin "2") (pinfunction "2_2") (pintype "passive"))
      (node (ref "XS1") (pin "10") (pinfunction "LED_10") (pintype "passive"))
    )
    (net (code "95") (name "Net-(XS1-SUSCLK)") (class "Default")
      (node (ref "XS1") (pin "68") (pinfunction "SUSCLK_68") (pintype "passive"))
      (node (ref "ZQ1") (pin "3") (pinfunction "OUTPUT_3") (pintype "output"))
    )
    (net (code "96") (name "unconnected-(DD1A-BT_~{DISABLE}-Pad91)") (class "Default")
      (node (ref "DD1") (pin "91") (pinfunction "BT_~{DISABLE}_91") (pintype "input+no_connect"))
    )
    (net (code "97") (name "unconnected-(DD1A-CAM_GPIO-Pad97)") (class "Default")
      (node (ref "DD1") (pin "97") (pinfunction "CAM_GPIO_97") (pintype "bidirectional+no_connect"))
    )
    (net (code "98") (name "unconnected-(DD1A-CAM_GPIO1-Pad100)") (class "Default")
      (node (ref "DD1") (pin "100") (pinfunction "CAM_GPIO1_100") (pintype "output+no_connect"))
    )
    (net (code "99") (name "unconnected-(DD1A-CM5_1.8V(OUTPUT)-Pad88)") (class "Default")
      (node (ref "DD1") (pin "88") (pinfunction "CM5_1.8V(OUTPUT)_88") (pintype "power_in+no_connect"))
    )
    (net (code "100") (name "unconnected-(DD1A-CM5_1.8V(OUTPUT)-Pad90)") (class "Default")
      (node (ref "DD1") (pin "90") (pinfunction "CM5_1.8V(OUTPUT)_90") (pintype "power_in+no_connect"))
    )
    (net (code "101") (name "unconnected-(DD1A-ETHERNET_SYNC_OUT-Pad18)") (class "Default")
      (node (ref "DD1") (pin "18") (pinfunction "ETHERNET_SYNC_OUT_18") (pintype "output+no_connect"))
    )
    (net (code "102") (name "unconnected-(DD1A-GPIO2-Pad58)") (class "Default")
      (node (ref "DD1") (pin "58") (pinfunction "GPIO2_58") (pintype "bidirectional+no_connect"))
    )
    (net (code "103") (name "unconnected-(DD1A-GPIO3-Pad56)") (class "Default")
      (node (ref "DD1") (pin "56") (pinfunction "GPIO3_56") (pintype "bidirectional+no_connect"))
    )
    (net (code "104") (name "unconnected-(DD1A-GPIO7-Pad37)") (class "Default")
      (node (ref "DD1") (pin "37") (pinfunction "GPIO7_37") (pintype "bidirectional+no_connect"))
    )
    (net (code "105") (name "unconnected-(DD1A-GPIO10-Pad44)") (class "Default")
      (node (ref "DD1") (pin "44") (pinfunction "GPIO10_44") (pintype "bidirectional+no_connect"))
    )
    (net (code "106") (name "unconnected-(DD1A-GPIO11-Pad38)") (class "Default")
      (node (ref "DD1") (pin "38") (pinfunction "GPIO11_38") (pintype "bidirectional+no_connect"))
    )
    (net (code "107") (name "unconnected-(DD1A-GPIO17-Pad50)") (class "Default")
      (node (ref "DD1") (pin "50") (pinfunction "GPIO17_50") (pintype "bidirectional+no_connect"))
    )
    (net (code "108") (name "unconnected-(DD1A-GPIO18-Pad49)") (class "Default")
      (node (ref "DD1") (pin "49") (pinfunction "GPIO18_49") (pintype "bidirectional+no_connect"))
    )
    (net (code "109") (name "unconnected-(DD1A-GPIO19-Pad26)") (class "Default")
      (node (ref "DD1") (pin "26") (pinfunction "GPIO19_26") (pintype "bidirectional+no_connect"))
    )
    (net (code "110") (name "unconnected-(DD1A-GPIO20-Pad27)") (class "Default")
      (node (ref "DD1") (pin "27") (pinfunction "GPIO20_27") (pintype "bidirectional+no_connect"))
    )
    (net (code "111") (name "unconnected-(DD1A-GPIO21-Pad25)") (class "Default")
      (node (ref "DD1") (pin "25") (pinfunction "GPIO21_25") (pintype "bidirectional+no_connect"))
    )
    (net (code "112") (name "unconnected-(DD1A-GPIO22-Pad46)") (class "Default")
      (node (ref "DD1") (pin "46") (pinfunction "GPIO22_46") (pintype "bidirectional+no_connect"))
    )
    (net (code "113") (name "unconnected-(DD1A-GPIO23-Pad47)") (class "Default")
      (node (ref "DD1") (pin "47") (pinfunction "GPIO23_47") (pintype "bidirectional+no_connect"))
    )
    (net (code "114") (name "unconnected-(DD1A-GPIO24-Pad45)") (class "Default")
      (node (ref "DD1") (pin "45") (pinfunction "GPIO24_45") (pintype "bidirectional+no_connect"))
    )
    (net (code "115") (name "unconnected-(DD1A-GPIO25-Pad41)") (class "Default")
      (node (ref "DD1") (pin "41") (pinfunction "GPIO25_41") (pintype "bidirectional+no_connect"))
    )
    (net (code "116") (name "unconnected-(DD1A-GPIO26-Pad24)") (class "Default")
      (node (ref "DD1") (pin "24") (pinfunction "GPIO26_24") (pintype "bidirectional+no_connect"))
    )
    (net (code "117") (name "unconnected-(DD1A-GPIO27-Pad48)") (class "Default")
      (node (ref "DD1") (pin "48") (pinfunction "GPIO27_48") (pintype "bidirectional+no_connect"))
    )
    (net (code "118") (name "unconnected-(DD1A-SCL0-Pad80)") (class "Default")
      (node (ref "DD1") (pin "80") (pinfunction "SCL0_80") (pintype "input+no_connect"))
    )
    (net (code "119") (name "unconnected-(DD1A-SDA0-Pad82)") (class "Default")
      (node (ref "DD1") (pin "82") (pinfunction "SDA0_82") (pintype "bidirectional+no_connect"))
    )
    (net (code "120") (name "unconnected-(DD1A-SD_DAT4-Pad68)") (class "Default")
      (node (ref "DD1") (pin "68") (pinfunction "SD_DAT4_68") (pintype "bidirectional+no_connect"))
    )
    (net (code "121") (name "unconnected-(DD1A-SD_DAT5-Pad64)") (class "Default")
      (node (ref "DD1") (pin "64") (pinfunction "SD_DAT5_64") (pintype "bidirectional+no_connect"))
    )
    (net (code "122") (name "unconnected-(DD1A-SD_DAT6-Pad72)") (class "Default")
      (node (ref "DD1") (pin "72") (pinfunction "SD_DAT6_72") (pintype "bidirectional+no_connect"))
    )
    (net (code "123") (name "unconnected-(DD1A-SD_DAT7-Pad70)") (class "Default")
      (node (ref "DD1") (pin "70") (pinfunction "SD_DAT7_70") (pintype "bidirectional+no_connect"))
    )
    (net (code "124") (name "unconnected-(DD1A-SD_VDD_OVERRIDE-Pad73)") (class "Default")
      (node (ref "DD1") (pin "73") (pinfunction "SD_VDD_OVERRIDE_73") (pintype "input+no_connect"))
    )
    (net (code "125") (name "unconnected-(DD1A-WL_~{DISABLE}-Pad89)") (class "Default")
      (node (ref "DD1") (pin "89") (pinfunction "WL_~{DISABLE}_89") (pintype "input+no_connect"))
    )
    (net (code "126") (name "unconnected-(DD1B-HDMI1_CEC-Pad149)") (class "Default")
      (node (ref "DD1") (pin "149") (pinfunction "HDMI1_CEC_149") (pintype "input+no_connect"))
    )
    (net (code "127") (name "unconnected-(DD1B-HDMI1_CLK_N-Pad166)") (class "Default")
      (node (ref "DD1") (pin "166") (pinfunction "HDMI1_CLK_N_166") (pintype "output+no_connect"))
    )
    (net (code "128") (name "unconnected-(DD1B-HDMI1_CLK_P-Pad164)") (class "Default")
      (node (ref "DD1") (pin "164") (pinfunction "HDMI1_CLK_P_164") (pintype "output+no_connect"))
    )
    (net (code "129") (name "unconnected-(DD1B-HDMI1_HOTPLUG-Pad143)") (class "Default")
      (node (ref "DD1") (pin "143") (pinfunction "HDMI1_HOTPLUG_143") (pintype "input+no_connect"))
    )
    (net (code "130") (name "unconnected-(DD1B-HDMI1_SCL-Pad147)") (class "Default")
      (node (ref "DD1") (pin "147") (pinfunction "HDMI1_SCL_147") (pintype "bidirectional+no_connect"))
    )
    (net (code "131") (name "unconnected-(DD1B-HDMI1_SDA-Pad145)") (class "Default")
      (node (ref "DD1") (pin "145") (pinfunction "HDMI1_SDA_145") (pintype "bidirectional+no_connect"))
    )
    (net (code "132") (name "unconnected-(DD1B-HDMI1_TX0_N-Pad160)") (class "Default")
      (node (ref "DD1") (pin "160") (pinfunction "HDMI1_TX0_N_160") (pintype "output+no_connect"))
    )
    (net (code "133") (name "unconnected-(DD1B-HDMI1_TX0_P-Pad158)") (class "Default")
      (node (ref "DD1") (pin "158") (pinfunction "HDMI1_TX0_P_158") (pintype "output+no_connect"))
    )
    (net (code "134") (name "unconnected-(DD1B-HDMI1_TX1_N-Pad154)") (class "Default")
      (node (ref "DD1") (pin "154") (pinfunction "HDMI1_TX1_N_154") (pintype "output+no_connect"))
    )
    (net (code "135") (name "unconnected-(DD1B-HDMI1_TX1_P-Pad152)") (class "Default")
      (node (ref "DD1") (pin "152") (pinfunction "HDMI1_TX1_P_152") (pintype "output+no_connect"))
    )
    (net (code "136") (name "unconnected-(DD1B-HDMI1_TX2_N-Pad148)") (class "Default")
      (node (ref "DD1") (pin "148") (pinfunction "HDMI1_TX2_N_148") (pintype "output+no_connect"))
    )
    (net (code "137") (name "unconnected-(DD1B-HDMI1_TX2_P-Pad146)") (class "Default")
      (node (ref "DD1") (pin "146") (pinfunction "HDMI1_TX2_P_146") (pintype "output+no_connect"))
    )
    (net (code "138") (name "unconnected-(DD1B-MIPI0_C_N-Pad127)") (class "Default")
      (node (ref "DD1") (pin "127") (pinfunction "MIPI0_C_N_127") (pintype "input+no_connect"))
    )
    (net (code "139") (name "unconnected-(DD1B-MIPI0_C_P-Pad129)") (class "Default")
      (node (ref "DD1") (pin "129") (pinfunction "MIPI0_C_P_129") (pintype "input+no_connect"))
    )
    (net (code "140") (name "unconnected-(DD1B-MIPI0_D0_N-Pad115)") (class "Default")
      (node (ref "DD1") (pin "115") (pinfunction "MIPI0_D0_N_115") (pintype "input+no_connect"))
    )
    (net (code "141") (name "unconnected-(DD1B-MIPI0_D0_P-Pad117)") (class "Default")
      (node (ref "DD1") (pin "117") (pinfunction "MIPI0_D0_P_117") (pintype "input+no_connect"))
    )
    (net (code "142") (name "unconnected-(DD1B-MIPI0_D1_N-Pad121)") (class "Default")
      (node (ref "DD1") (pin "121") (pinfunction "MIPI0_D1_N_121") (pintype "input+no_connect"))
    )
    (net (code "143") (name "unconnected-(DD1B-MIPI0_D1_P-Pad123)") (class "Default")
      (node (ref "DD1") (pin "123") (pinfunction "MIPI0_D1_P_123") (pintype "input+no_connect"))
    )
    (net (code "144") (name "unconnected-(DD1B-MIPI0_D2_N-Pad133)") (class "Default")
      (node (ref "DD1") (pin "133") (pinfunction "MIPI0_D2_N_133") (pintype "input+no_connect"))
    )
    (net (code "145") (name "unconnected-(DD1B-MIPI0_D2_P-Pad135)") (class "Default")
      (node (ref "DD1") (pin "135") (pinfunction "MIPI0_D2_P_135") (pintype "input+no_connect"))
    )
    (net (code "146") (name "unconnected-(DD1B-MIPI0_D3_N-Pad139)") (class "Default")
      (node (ref "DD1") (pin "139") (pinfunction "MIPI0_D3_N_139") (pintype "input+no_connect"))
    )
    (net (code "147") (name "unconnected-(DD1B-MIPI0_D3_P-Pad141)") (class "Default")
      (node (ref "DD1") (pin "141") (pinfunction "MIPI0_D3_P_141") (pintype "input+no_connect"))
    )
    (net (code "148") (name "unconnected-(DD1B-MIPI1_C_N-Pad187)") (class "Default")
      (node (ref "DD1") (pin "187") (pinfunction "MIPI1_C_N_187") (pintype "output+no_connect"))
    )
    (net (code "149") (name "unconnected-(DD1B-MIPI1_C_P-Pad189)") (class "Default")
      (node (ref "DD1") (pin "189") (pinfunction "MIPI1_C_P_189") (pintype "output+no_connect"))
    )
    (net (code "150") (name "unconnected-(DD1B-MIPI1_D0_N-Pad175)") (class "Default")
      (node (ref "DD1") (pin "175") (pinfunction "MIPI1_D0_N_175") (pintype "output+no_connect"))
    )
    (net (code "151") (name "unconnected-(DD1B-MIPI1_D0_P-Pad177)") (class "Default")
      (node (ref "DD1") (pin "177") (pinfunction "MIPI1_D0_P_177") (pintype "output+no_connect"))
    )
    (net (code "152") (name "unconnected-(DD1B-MIPI1_D1_N-Pad181)") (class "Default")
      (node (ref "DD1") (pin "181") (pinfunction "MIPI1_D1_N_181") (pintype "output+no_connect"))
    )
    (net (code "153") (name "unconnected-(DD1B-MIPI1_D1_P-Pad183)") (class "Default")
      (node (ref "DD1") (pin "183") (pinfunction "MIPI1_D1_P_183") (pintype "output+no_connect"))
    )
    (net (code "154") (name "unconnected-(DD1B-MIPI1_D2_N-Pad193)") (class "Default")
      (node (ref "DD1") (pin "193") (pinfunction "MIPI1_D2_N_193") (pintype "output+no_connect"))
    )
    (net (code "155") (name "unconnected-(DD1B-MIPI1_D2_P-Pad195)") (class "Default")
      (node (ref "DD1") (pin "195") (pinfunction "MIPI1_D2_P_195") (pintype "output+no_connect"))
    )
    (net (code "156") (name "unconnected-(DD1B-MIPI1_D3_N-Pad194)") (class "Default")
      (node (ref "DD1") (pin "194") (pinfunction "MIPI1_D3_N_194") (pintype "output+no_connect"))
    )
    (net (code "157") (name "unconnected-(DD1B-MIPI1_D3_P-Pad196)") (class "Default")
      (node (ref "DD1") (pin "196") (pinfunction "MIPI1_D3_P_196") (pintype "output+no_connect"))
    )
    (net (code "158") (name "unconnected-(DD1B-VBUS_EN-Pad111)") (class "Default")
      (node (ref "DD1") (pin "111") (pinfunction "VBUS_EN_111") (pintype "output"))
    )
    (net (code "159") (name "unconnected-(DD2-NC-Pad5)") (class "Default")
      (node (ref "DD2") (pin "5") (pinfunction "NC_5") (pintype "passive+no_connect"))
    )
    (net (code "160") (name "unconnected-(XS1-DEVSLP-Pad38)") (class "Default")
      (node (ref "XS1") (pin "38") (pinfunction "DEVSLP_38") (pintype "passive+no_connect"))
    )
    (net (code "161") (name "unconnected-(XS1-PEDET-Pad69)") (class "Default")
      (node (ref "XS1") (pin "69") (pinfunction "PEDET_69") (pintype "passive+no_connect"))
    )
    (net (code "162") (name "unconnected-(XS1-PER_N_1-Pad35)") (class "Default")
      (node (ref "XS1") (pin "35") (pinfunction "PER_N_1_35") (pintype "passive+no_connect"))
    )
    (net (code "163") (name "unconnected-(XS1-PER_N_2-Pad23)") (class "Default")
      (node (ref "XS1") (pin "23") (pinfunction "PER_N_2_23") (pintype "passive+no_connect"))
    )
    (net (code "164") (name "unconnected-(XS1-PER_N_3-Pad11)") (class "Default")
      (node (ref "XS1") (pin "11") (pinfunction "PER_N_3_11") (pintype "passive+no_connect"))
    )
    (net (code "165") (name "unconnected-(XS1-PER_P_1-Pad37)") (class "Default")
      (node (ref "XS1") (pin "37") (pinfunction "PER_P_1_37") (pintype "passive+no_connect"))
    )
    (net (code "166") (name "unconnected-(XS1-PER_P_2-Pad25)") (class "Default")
      (node (ref "XS1") (pin "25") (pinfunction "PER_P_2_25") (pintype "passive+no_connect"))
    )
    (net (code "167") (name "unconnected-(XS1-PER_P_3-Pad13)") (class "Default")
      (node (ref "XS1") (pin "13") (pinfunction "PER_P_3_13") (pintype "passive+no_connect"))
    )
    (net (code "168") (name "unconnected-(XS1-PET_N_1-Pad29)") (class "Default")
      (node (ref "XS1") (pin "29") (pinfunction "PET_N_1_29") (pintype "passive+no_connect"))
    )
    (net (code "169") (name "unconnected-(XS1-PET_N_2-Pad17)") (class "Default")
      (node (ref "XS1") (pin "17") (pinfunction "PET_N_2_17") (pintype "passive+no_connect"))
    )
    (net (code "170") (name "unconnected-(XS1-PET_N_3-Pad5)") (class "Default")
      (node (ref "XS1") (pin "5") (pinfunction "PET_N_3_5") (pintype "passive+no_connect"))
    )
    (net (code "171") (name "unconnected-(XS1-PET_P_1-Pad31)") (class "Default")
      (node (ref "XS1") (pin "31") (pinfunction "PET_P_1_31") (pintype "passive+no_connect"))
    )
    (net (code "172") (name "unconnected-(XS1-PET_P_2-Pad19)") (class "Default")
      (node (ref "XS1") (pin "19") (pinfunction "PET_P_2_19") (pintype "passive+no_connect"))
    )
    (net (code "173") (name "unconnected-(XS1-PET_P_3-Pad7)") (class "Default")
      (node (ref "XS1") (pin "7") (pinfunction "PET_P_3_7") (pintype "passive+no_connect"))
    )
  )
)
